# sign.net
KiCad netlist of a schematic drawn in EAGLE
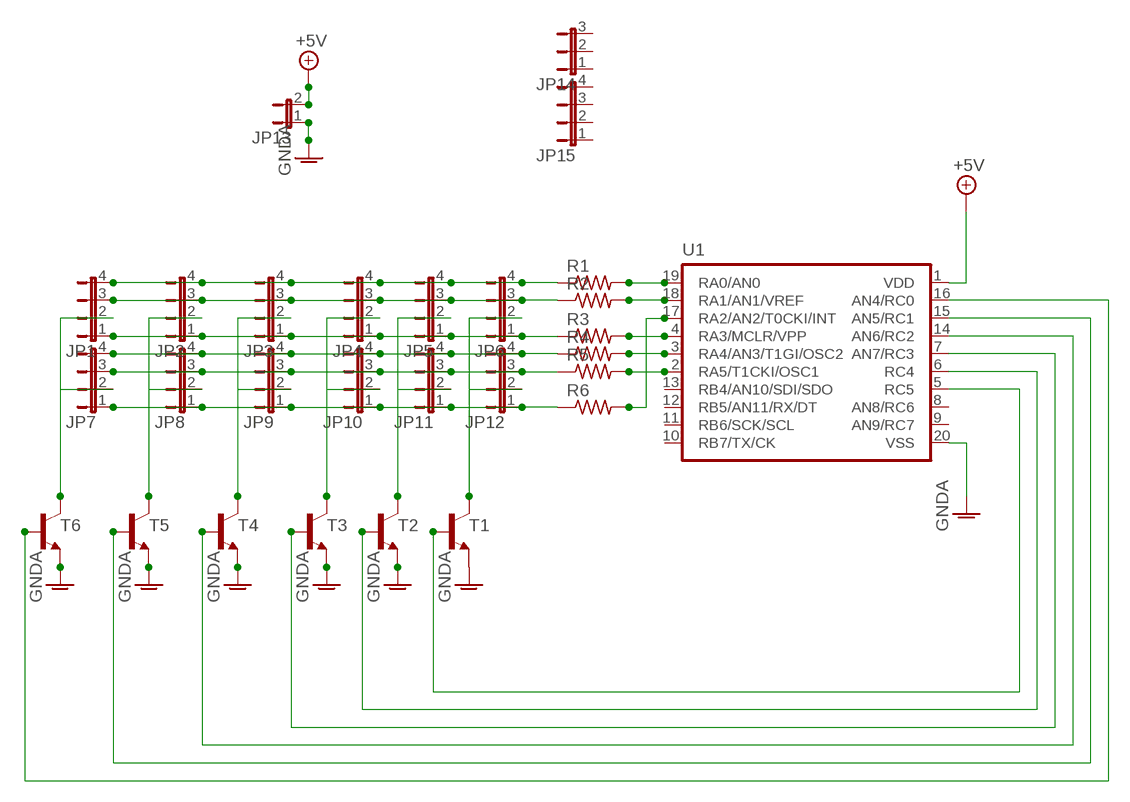
[diagram p0: schematic, sheet 1]

(export (version "E")
  (design (tool "Eeschema 10.0.6"))
  (components
    (comp (ref "JP1")
      (value "JP4E")
      (footprint "eagle-import:JP4")
      (libsource (lib "eagle-import") (part "JP4E"))
    )
    (comp (ref "JP2")
      (value "JP4E")
      (footprint "eagle-import:JP4")
      (libsource (lib "eagle-import") (part "JP4E"))
    )
    (comp (ref "JP3")
      (value "JP4E")
      (footprint "eagle-import:JP4")
      (libsource (lib "eagle-import") (part "JP4E"))
    )
    (comp (ref "JP4")
      (value "JP4E")
      (footprint "eagle-import:JP4")
      (libsource (lib "eagle-import") (part "JP4E"))
    )
    (comp (ref "JP5")
      (value "JP4E")
      (footprint "eagle-import:JP4")
      (libsource (lib "eagle-import") (part "JP4E"))
    )
    (comp (ref "JP6")
      (value "JP4E")
      (footprint "eagle-import:JP4")
      (libsource (lib "eagle-import") (part "JP4E"))
    )
    (comp (ref "JP7")
      (value "JP4E")
      (footprint "eagle-import:JP4")
      (libsource (lib "eagle-import") (part "JP4E"))
    )
    (comp (ref "JP8")
      (value "JP4E")
      (footprint "eagle-import:JP4")
      (libsource (lib "eagle-import") (part "JP4E"))
    )
    (comp (ref "JP9")
      (value "JP4E")
      (footprint "eagle-import:JP4")
      (libsource (lib "eagle-import") (part "JP4E"))
    )
    (comp (ref "JP10")
      (value "JP4E")
      (footprint "eagle-import:JP4")
      (libsource (lib "eagle-import") (part "JP4E"))
    )
    (comp (ref "JP11")
      (value "JP4E")
      (footprint "eagle-import:JP4")
      (libsource (lib "eagle-import") (part "JP4E"))
    )
    (comp (ref "JP12")
      (value "JP4E")
      (footprint "eagle-import:JP4")
      (libsource (lib "eagle-import") (part "JP4E"))
    )
    (comp (ref "JP13")
      (value "JP1E")
      (footprint "eagle-import:JP1")
      (libsource (lib "eagle-import") (part "JP1E"))
    )
    (comp (ref "JP14")
      (value "JP2E")
      (footprint "eagle-import:JP2")
      (libsource (lib "eagle-import") (part "JP2E"))
    )
    (comp (ref "JP15")
      (value "JP4E")
      (footprint "eagle-import:JP4")
      (libsource (lib "eagle-import") (part "JP4E"))
    )
    (comp (ref "R1")
      (value "R-US_0207/10")
      (footprint "eagle-import:0207_10")
      (libsource (lib "eagle-import") (part "R-US_0207/10"))
    )
    (comp (ref "R2")
      (value "R-US_0207/10")
      (footprint "eagle-import:0207_10")
      (libsource (lib "eagle-import") (part "R-US_0207/10"))
    )
    (comp (ref "R3")
      (value "R-US_0207/10")
      (footprint "eagle-import:0207_10")
      (libsource (lib "eagle-import") (part "R-US_0207/10"))
    )
    (comp (ref "R4")
      (value "R-US_0207/10")
      (footprint "eagle-import:0207_10")
      (libsource (lib "eagle-import") (part "R-US_0207/10"))
    )
    (comp (ref "R5")
      (value "R-US_0207/10")
      (footprint "eagle-import:0207_10")
      (libsource (lib "eagle-import") (part "R-US_0207/10"))
    )
    (comp (ref "R6")
      (value "R-US_0207/10")
      (footprint "eagle-import:0207_10")
      (libsource (lib "eagle-import") (part "R-US_0207/10"))
    )
    (comp (ref "T1")
      (value "-NPN-TO92")
      (footprint "eagle-import:TO92")
      (libsource (lib "eagle-import") (part "-NPN-TO92"))
    )
    (comp (ref "T2")
      (value "-NPN-TO92")
      (footprint "eagle-import:TO92")
      (libsource (lib "eagle-import") (part "-NPN-TO92"))
    )
    (comp (ref "T3")
      (value "-NPN-TO92")
      (footprint "eagle-import:TO92")
      (libsource (lib "eagle-import") (part "-NPN-TO92"))
    )
    (comp (ref "T4")
      (value "-NPN-TO92")
      (footprint "eagle-import:TO92")
      (libsource (lib "eagle-import") (part "-NPN-TO92"))
    )
    (comp (ref "T5")
      (value "-NPN-TO92")
      (footprint "eagle-import:TO92")
      (libsource (lib "eagle-import") (part "-NPN-TO92"))
    )
    (comp (ref "T6")
      (value "-NPN-TO92")
      (footprint "eagle-import:TO92")
      (libsource (lib "eagle-import") (part "-NPN-TO92"))
    )
    (comp (ref "U1")
      (value "PIC16F6XX")
      (footprint "eagle-import:DIL20")
      (libsource (lib "eagle-import") (part "PIC16F6XX"))
    )
  )
  (nets
    (net (code "1") (name "+5V") (class "Default")
      (node (ref "JP13") (pin "2") (pinfunction "2_2") (pintype "passive"))
      (node (ref "U1") (pin "1") (pinfunction "VDD_1") (pintype "power_in"))
    )
    (net (code "2") (name "GNDA") (class "Default")
      (node (ref "JP13") (pin "1") (pinfunction "1_1") (pintype "passive"))
      (node (ref "T1") (pin "1") (pinfunction "E_1") (pintype "passive"))
      (node (ref "T2") (pin "1") (pinfunction "E_1") (pintype "passive"))
      (node (ref "T3") (pin "1") (pinfunction "E_1") (pintype "passive"))
      (node (ref "T4") (pin "1") (pinfunction "E_1") (pintype "passive"))
      (node (ref "T5") (pin "1") (pinfunction "E_1") (pintype "passive"))
      (node (ref "T6") (pin "1") (pinfunction "E_1") (pintype "passive"))
      (node (ref "U1") (pin "20") (pinfunction "VSS_20") (pintype "power_in"))
    )
    (net (code "3") (name "Net-(JP1-Pad1)") (class "Default")
      (node (ref "JP1") (pin "1") (pinfunction "1_1") (pintype "passive"))
      (node (ref "JP2") (pin "1") (pinfunction "1_1") (pintype "passive"))
      (node (ref "JP3") (pin "1") (pinfunction "1_1") (pintype "passive"))
      (node (ref "JP4") (pin "1") (pinfunction "1_1") (pintype "passive"))
      (node (ref "JP5") (pin "1") (pinfunction "1_1") (pintype "passive"))
      (node (ref "JP6") (pin "1") (pinfunction "1_1") (pintype "passive"))
      (node (ref "R3") (pin "1") (pinfunction "1_1") (pintype "passive"))
    )
    (net (code "4") (name "Net-(JP1-Pad3)") (class "Default")
      (node (ref "JP1") (pin "3") (pinfunction "3_3") (pintype "passive"))
      (node (ref "JP2") (pin "3") (pinfunction "3_3") (pintype "passive"))
      (node (ref "JP3") (pin "3") (pinfunction "3_3") (pintype "passive"))
      (node (ref "JP4") (pin "3") (pinfunction "3_3") (pintype "passive"))
      (node (ref "JP5") (pin "3") (pinfunction "3_3") (pintype "passive"))
      (node (ref "JP6") (pin "3") (pinfunction "3_3") (pintype "passive"))
      (node (ref "R2") (pin "1") (pinfunction "1_1") (pintype "passive"))
    )
    (net (code "5") (name "Net-(JP1-Pad4)") (class "Default")
      (node (ref "JP1") (pin "4") (pinfunction "4_4") (pintype "passive"))
      (node (ref "JP2") (pin "4") (pinfunction "4_4") (pintype "passive"))
      (node (ref "JP3") (pin "4") (pinfunction "4_4") (pintype "passive"))
      (node (ref "JP4") (pin "4") (pinfunction "4_4") (pintype "passive"))
      (node (ref "JP5") (pin "4") (pinfunction "4_4") (pintype "passive"))
      (node (ref "JP6") (pin "4") (pinfunction "4_4") (pintype "passive"))
      (node (ref "R1") (pin "1") (pinfunction "1_1") (pintype "passive"))
    )
    (net (code "6") (name "Net-(JP10-Pad1)") (class "Default")
      (node (ref "JP10") (pin "1") (pinfunction "1_1") (pintype "passive"))
      (node (ref "JP11") (pin "1") (pinfunction "1_1") (pintype "passive"))
      (node (ref "JP12") (pin "1") (pinfunction "1_1") (pintype "passive"))
      (node (ref "JP7") (pin "1") (pinfunction "1_1") (pintype "passive"))
      (node (ref "JP8") (pin "1") (pinfunction "1_1") (pintype "passive"))
      (node (ref "JP9") (pin "1") (pinfunction "1_1") (pintype "passive"))
      (node (ref "R6") (pin "1") (pinfunction "1_1") (pintype "passive"))
    )
    (net (code "7") (name "Net-(JP10-Pad3)") (class "Default")
      (node (ref "JP10") (pin "3") (pinfunction "3_3") (pintype "passive"))
      (node (ref "JP11") (pin "3") (pinfunction "3_3") (pintype "passive"))
      (node (ref "JP12") (pin "3") (pinfunction "3_3") (pintype "passive"))
      (node (ref "JP7") (pin "3") (pinfunction "3_3") (pintype "passive"))
      (node (ref "JP8") (pin "3") (pinfunction "3_3") (pintype "passive"))
      (node (ref "JP9") (pin "3") (pinfunction "3_3") (pintype "passive"))
      (node (ref "R5") (pin "1") (pinfunction "1_1") (pintype "passive"))
    )
    (net (code "8") (name "Net-(JP10-Pad4)") (class "Default")
      (node (ref "JP10") (pin "4") (pinfunction "4_4") (pintype "passive"))
      (node (ref "JP11") (pin "4") (pinfunction "4_4") (pintype "passive"))
      (node (ref "JP12") (pin "4") (pinfunction "4_4") (pintype "passive"))
      (node (ref "JP7") (pin "4") (pinfunction "4_4") (pintype "passive"))
      (node (ref "JP8") (pin "4") (pinfunction "4_4") (pintype "passive"))
      (node (ref "JP9") (pin "4") (pinfunction "4_4") (pintype "passive"))
      (node (ref "R4") (pin "1") (pinfunction "1_1") (pintype "passive"))
    )
    (net (code "9") (name "Net-(T1-B)") (class "Default")
      (node (ref "T1") (pin "2") (pinfunction "B_2") (pintype "passive"))
      (node (ref "U1") (pin "5") (pinfunction "RC5_5") (pintype "bidirectional"))
    )
    (net (code "10") (name "Net-(T1-C)") (class "Default")
      (node (ref "JP12") (pin "2") (pinfunction "2_2") (pintype "passive"))
      (node (ref "JP6") (pin "2") (pinfunction "2_2") (pintype "passive"))
      (node (ref "T1") (pin "3") (pinfunction "C_3") (pintype "passive"))
    )
    (net (code "11") (name "Net-(T2-B)") (class "Default")
      (node (ref "T2") (pin "2") (pinfunction "B_2") (pintype "passive"))
      (node (ref "U1") (pin "6") (pinfunction "RC4_6") (pintype "bidirectional"))
    )
    (net (code "12") (name "Net-(T2-C)") (class "Default")
      (node (ref "JP11") (pin "2") (pinfunction "2_2") (pintype "passive"))
      (node (ref "JP5") (pin "2") (pinfunction "2_2") (pintype "passive"))
      (node (ref "T2") (pin "3") (pinfunction "C_3") (pintype "passive"))
    )
    (net (code "13") (name "Net-(T3-B)") (class "Default")
      (node (ref "T3") (pin "2") (pinfunction "B_2") (pintype "passive"))
      (node (ref "U1") (pin "7") (pinfunction "AN7/RC3_7") (pintype "bidirectional"))
    )
    (net (code "14") (name "Net-(T3-C)") (class "Default")
      (node (ref "JP10") (pin "2") (pinfunction "2_2") (pintype "passive"))
      (node (ref "JP4") (pin "2") (pinfunction "2_2") (pintype "passive"))
      (node (ref "T3") (pin "3") (pinfunction "C_3") (pintype "passive"))
    )
    (net (code "15") (name "Net-(T4-B)") (class "Default")
      (node (ref "T4") (pin "2") (pinfunction "B_2") (pintype "passive"))
      (node (ref "U1") (pin "14") (pinfunction "AN6/RC2_14") (pintype "bidirectional"))
    )
    (net (code "16") (name "Net-(T4-C)") (class "Default")
      (node (ref "JP3") (pin "2") (pinfunction "2_2") (pintype "passive"))
      (node (ref "JP9") (pin "2") (pinfunction "2_2") (pintype "passive"))
      (node (ref "T4") (pin "3") (pinfunction "C_3") (pintype "passive"))
    )
    (net (code "17") (name "Net-(T5-B)") (class "Default")
      (node (ref "T5") (pin "2") (pinfunction "B_2") (pintype "passive"))
      (node (ref "U1") (pin "15") (pinfunction "AN5/RC1_15") (pintype "bidirectional"))
    )
    (net (code "18") (name "Net-(T5-C)") (class "Default")
      (node (ref "JP2") (pin "2") (pinfunction "2_2") (pintype "passive"))
      (node (ref "JP8") (pin "2") (pinfunction "2_2") (pintype "passive"))
      (node (ref "T5") (pin "3") (pinfunction "C_3") (pintype "passive"))
    )
    (net (code "19") (name "Net-(T6-B)") (class "Default")
      (node (ref "T6") (pin "2") (pinfunction "B_2") (pintype "passive"))
      (node (ref "U1") (pin "16") (pinfunction "AN4/RC0_16") (pintype "bidirectional"))
    )
    (net (code "20") (name "Net-(T6-C)") (class "Default")
      (node (ref "JP1") (pin "2") (pinfunction "2_2") (pintype "passive"))
      (node (ref "JP7") (pin "2") (pinfunction "2_2") (pintype "passive"))
      (node (ref "T6") (pin "3") (pinfunction "C_3") (pintype "passive"))
    )
    (net (code "21") (name "Net-(U1-RA0{slash}AN0)") (class "Default")
      (node (ref "R1") (pin "2") (pinfunction "2_2") (pintype "passive"))
      (node (ref "U1") (pin "19") (pinfunction "RA0/AN0_19") (pintype "bidirectional"))
    )
    (net (code "22") (name "Net-(U1-RA1{slash}AN1{slash}VREF)") (class "Default")
      (node (ref "R2") (pin "2") (pinfunction "2_2") (pintype "passive"))
      (node (ref "U1") (pin "18") (pinfunction "RA1/AN1/VREF_18") (pintype "bidirectional"))
    )
    (net (code "23") (name "Net-(U1-RA2{slash}AN2{slash}T0CKI{slash}INT)") (class "Default")
      (node (ref "R6") (pin "2") (pinfunction "2_2") (pintype "passive"))
      (node (ref "U1") (pin "17") (pinfunction "RA2/AN2/T0CKI/INT_17") (pintype "bidirectional"))
    )
    (net (code "24") (name "Net-(U1-RA3{slash}MCLR{slash}VPP)") (class "Default")
      (node (ref "R3") (pin "2") (pinfunction "2_2") (pintype "passive"))
      (node (ref "U1") (pin "4") (pinfunction "RA3/MCLR/VPP_4") (pintype "input"))
    )
    (net (code "25") (name "Net-(U1-RA4{slash}AN3{slash}T1GI{slash}OSC2)") (class "Default")
      (node (ref "R4") (pin "2") (pinfunction "2_2") (pintype "passive"))
      (node (ref "U1") (pin "3") (pinfunction "RA4/AN3/T1GI/OSC2_3") (pintype "bidirectional"))
    )
    (net (code "26") (name "Net-(U1-RA5{slash}T1CKI{slash}OSC1)") (class "Default")
      (node (ref "R5") (pin "2") (pinfunction "2_2") (pintype "passive"))
      (node (ref "U1") (pin "2") (pinfunction "RA5/T1CKI/OSC1_2") (pintype "bidirectional"))
    )
    (net (code "27") (name "unconnected-(JP14-Pad1)") (class "Default")
      (node (ref "JP14") (pin "1") (pinfunction "1_1") (pintype "passive"))
    )
    (net (code "28") (name "unconnected-(JP14-Pad2)") (class "Default")
      (node (ref "JP14") (pin "2") (pinfunction "2_2") (pintype "passive"))
    )
    (net (code "29") (name "unconnected-(JP14-Pad3)") (class "Default")
      (node (ref "JP14") (pin "3") (pinfunction "3_3") (pintype "passive"))
    )
    (net (code "30") (name "unconnected-(JP15-Pad1)") (class "Default")
      (node (ref "JP15") (pin "1") (pinfunction "1_1") (pintype "passive"))
    )
    (net (code "31") (name "unconnected-(JP15-Pad2)") (class "Default")
      (node (ref "JP15") (pin "2") (pinfunction "2_2") (pintype "passive"))
    )
    (net (code "32") (name "unconnected-(JP15-Pad3)") (class "Default")
      (node (ref "JP15") (pin "3") (pinfunction "3_3") (pintype "passive"))
    )
    (net (code "33") (name "unconnected-(JP15-Pad4)") (class "Default")
      (node (ref "JP15") (pin "4") (pinfunction "4_4") (pintype "passive"))
    )
    (net (code "34") (name "unconnected-(U1-AN8{slash}RC6-Pad8)") (class "Default")
      (node (ref "U1") (pin "8") (pinfunction "AN8/RC6_8") (pintype "bidirectional"))
    )
    (net (code "35") (name "unconnected-(U1-AN9{slash}RC7-Pad9)") (class "Default")
      (node (ref "U1") (pin "9") (pinfunction "AN9/RC7_9") (pintype "bidirectional"))
    )
    (net (code "36") (name "unconnected-(U1-RB4{slash}AN10{slash}SDI{slash}SDO-Pad13)") (class "Default")
      (node (ref "U1") (pin "13") (pinfunction "RB4/AN10/SDI/SDO_13") (pintype "bidirectional"))
    )
    (net (code "37") (name "unconnected-(U1-RB5{slash}AN11{slash}RX{slash}DT-Pad12)") (class "Default")
      (node (ref "U1") (pin "12") (pinfunction "RB5/AN11/RX/DT_12") (pintype "bidirectional"))
    )
    (net (code "38") (name "unconnected-(U1-RB6{slash}SCK{slash}SCL-Pad11)") (class "Default")
      (node (ref "U1") (pin "11") (pinfunction "RB6/SCK/SCL_11") (pintype "bidirectional"))
    )
    (net (code "39") (name "unconnected-(U1-RB7{slash}TX{slash}CK-Pad10)") (class "Default")
      (node (ref "U1") (pin "10") (pinfunction "RB7/TX/CK_10") (pintype "bidirectional"))
    )
  )
)
